# shield.net
KiCad netlist of a schematic drawn in EAGLE
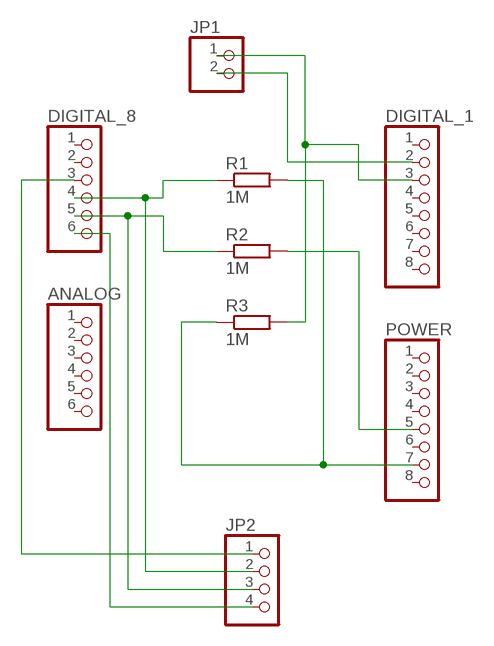
[diagram p0: schematic, sheet 1]

(export (version "E")
  (design (tool "Eeschema 10.0.6"))
  (components
    (comp (ref "ANALOG")
      (value "PINHD-1X6")
      (footprint "eagle-import:1X06")
      (libsource (lib "eagle-import") (part "PINHD-1X6"))
    )
    (comp (ref "DIGITAL_1")
      (value "PINHD-1X8")
      (footprint "eagle-import:1X08")
      (libsource (lib "eagle-import") (part "PINHD-1X8"))
    )
    (comp (ref "DIGITAL_8")
      (value "PINHD-1X6")
      (footprint "eagle-import:1X06")
      (libsource (lib "eagle-import") (part "PINHD-1X6"))
    )
    (comp (ref "JP1")
      (value "PINHD-1X2")
      (footprint "eagle-import:1X02")
      (libsource (lib "eagle-import") (part "PINHD-1X2"))
    )
    (comp (ref "JP2")
      (value "PINHD-1X4")
      (footprint "eagle-import:1X04")
      (libsource (lib "eagle-import") (part "PINHD-1X4"))
    )
    (comp (ref "POWER")
      (value "PINHD-1X8")
      (footprint "eagle-import:1X08")
      (libsource (lib "eagle-import") (part "PINHD-1X8"))
    )
    (comp (ref "R1")
      (value "1M")
      (footprint "eagle-import:0207_10")
      (libsource (lib "eagle-import") (part "R-EU_0207/10"))
    )
    (comp (ref "R2")
      (value "1M")
      (footprint "eagle-import:0207_10")
      (libsource (lib "eagle-import") (part "R-EU_0207/10"))
    )
    (comp (ref "R3")
      (value "1M")
      (footprint "eagle-import:0207_10")
      (libsource (lib "eagle-import") (part "R-EU_0207/10"))
    )
  )
  (nets
    (net (code "1") (name "Net-(DIGITAL_1-Pad2)") (class "Default")
      (node (ref "DIGITAL_1") (pin "2") (pinfunction "2_2") (pintype "passive"))
      (node (ref "JP1") (pin "2") (pinfunction "2_2") (pintype "passive"))
    )
    (net (code "2") (name "Net-(DIGITAL_1-Pad3)") (class "Default")
      (node (ref "DIGITAL_1") (pin "3") (pinfunction "3_3") (pintype "passive"))
      (node (ref "JP1") (pin "1") (pinfunction "1_1") (pintype "passive"))
      (node (ref "R3") (pin "2") (pinfunction "2_2") (pintype "passive"))
    )
    (net (code "3") (name "Net-(DIGITAL_8-Pad3)") (class "Default")
      (node (ref "DIGITAL_8") (pin "3") (pinfunction "3_3") (pintype "passive"))
      (node (ref "JP2") (pin "1") (pinfunction "1_1") (pintype "passive"))
    )
    (net (code "4") (name "Net-(DIGITAL_8-Pad4)") (class "Default")
      (node (ref "DIGITAL_8") (pin "4") (pinfunction "4_4") (pintype "passive"))
      (node (ref "JP2") (pin "2") (pinfunction "2_2") (pintype "passive"))
      (node (ref "R1") (pin "1") (pinfunction "1_1") (pintype "passive"))
    )
    (net (code "5") (name "Net-(DIGITAL_8-Pad5)") (class "Default")
      (node (ref "DIGITAL_8") (pin "5") (pinfunction "5_5") (pintype "passive"))
      (node (ref "JP2") (pin "3") (pinfunction "3_3") (pintype "passive"))
      (node (ref "R2") (pin "1") (pinfunction "1_1") (pintype "passive"))
    )
    (net (code "6") (name "Net-(DIGITAL_8-Pad6)") (class "Default")
      (node (ref "DIGITAL_8") (pin "6") (pinfunction "6_6") (pintype "passive"))
      (node (ref "JP2") (pin "4") (pinfunction "4_4") (pintype "passive"))
    )
    (net (code "7") (name "Net-(POWER-Pad5)") (class "Default")
      (node (ref "POWER") (pin "5") (pinfunction "5_5") (pintype "passive"))
      (node (ref "R2") (pin "2") (pinfunction "2_2") (pintype "passive"))
    )
    (net (code "8") (name "Net-(POWER-Pad7)") (class "Default")
      (node (ref "POWER") (pin "7") (pinfunction "7_7") (pintype "passive"))
      (node (ref "R1") (pin "2") (pinfunction "2_2") (pintype "passive"))
      (node (ref "R3") (pin "1") (pinfunction "1_1") (pintype "passive"))
    )
    (net (code "9") (name "unconnected-(ANALOG-Pad1)") (class "Default")
      (node (ref "ANALOG") (pin "1") (pinfunction "1_1") (pintype "passive"))
    )
    (net (code "10") (name "unconnected-(ANALOG-Pad2)") (class "Default")
      (node (ref "ANALOG") (pin "2") (pinfunction "2_2") (pintype "passive"))
    )
    (net (code "11") (name "unconnected-(ANALOG-Pad3)") (class "Default")
      (node (ref "ANALOG") (pin "3") (pinfunction "3_3") (pintype "passive"))
    )
    (net (code "12") (name "unconnected-(ANALOG-Pad4)") (class "Default")
      (node (ref "ANALOG") (pin "4") (pinfunction "4_4") (pintype "passive"))
    )
    (net (code "13") (name "unconnected-(ANALOG-Pad5)") (class "Default")
      (node (ref "ANALOG") (pin "5") (pinfunction "5_5") (pintype "passive"))
    )
    (net (code "14") (name "unconnected-(ANALOG-Pad6)") (class "Default")
      (node (ref "ANALOG") (pin "6") (pinfunction "6_6") (pintype "passive"))
    )
    (net (code "15") (name "unconnected-(DIGITAL_1-Pad1)") (class "Default")
      (node (ref "DIGITAL_1") (pin "1") (pinfunction "1_1") (pintype "passive"))
    )
    (net (code "16") (name "unconnected-(DIGITAL_1-Pad4)") (class "Default")
      (node (ref "DIGITAL_1") (pin "4") (pinfunction "4_4") (pintype "passive"))
    )
    (net (code "17") (name "unconnected-(DIGITAL_1-Pad5)") (class "Default")
      (node (ref "DIGITAL_1") (pin "5") (pinfunction "5_5") (pintype "passive"))
    )
    (net (code "18") (name "unconnected-(DIGITAL_1-Pad6)") (class "Default")
      (node (ref "DIGITAL_1") (pin "6") (pinfunction "6_6") (pintype "passive"))
    )
    (net (code "19") (name "unconnected-(DIGITAL_1-Pad7)") (class "Default")
      (node (ref "DIGITAL_1") (pin "7") (pinfunction "7_7") (pintype "passive"))
    )
    (net (code "20") (name "unconnected-(DIGITAL_1-Pad8)") (class "Default")
      (node (ref "DIGITAL_1") (pin "8") (pinfunction "8_8") (pintype "passive"))
    )
    (net (code "21") (name "unconnected-(DIGITAL_8-Pad1)") (class "Default")
      (node (ref "DIGITAL_8") (pin "1") (pinfunction "1_1") (pintype "passive"))
    )
    (net (code "22") (name "unconnected-(DIGITAL_8-Pad2)") (class "Default")
      (node (ref "DIGITAL_8") (pin "2") (pinfunction "2_2") (pintype "passive"))
    )
    (net (code "23") (name "unconnected-(POWER-Pad1)") (class "Default")
      (node (ref "POWER") (pin "1") (pinfunction "1_1") (pintype "passive"))
    )
    (net (code "24") (name "unconnected-(POWER-Pad2)") (class "Default")
      (node (ref "POWER") (pin "2") (pinfunction "2_2") (pintype "passive"))
    )
    (net (code "25") (name "unconnected-(POWER-Pad3)") (class "Default")
      (node (ref "POWER") (pin "3") (pinfunction "3_3") (pintype "passive"))
    )
    (net (code "26") (name "unconnected-(POWER-Pad4)") (class "Default")
      (node (ref "POWER") (pin "4") (pinfunction "4_4") (pintype "passive"))
    )
    (net (code "27") (name "unconnected-(POWER-Pad6)") (class "Default")
      (node (ref "POWER") (pin "6") (pinfunction "6_6") (pintype "passive"))
    )
    (net (code "28") (name "unconnected-(POWER-Pad8)") (class "Default")
      (node (ref "POWER") (pin "8") (pinfunction "8_8") (pintype "passive"))
    )
  )
)
